# MainInterface.net
KiCad netlist of a schematic drawn in Altium Designer
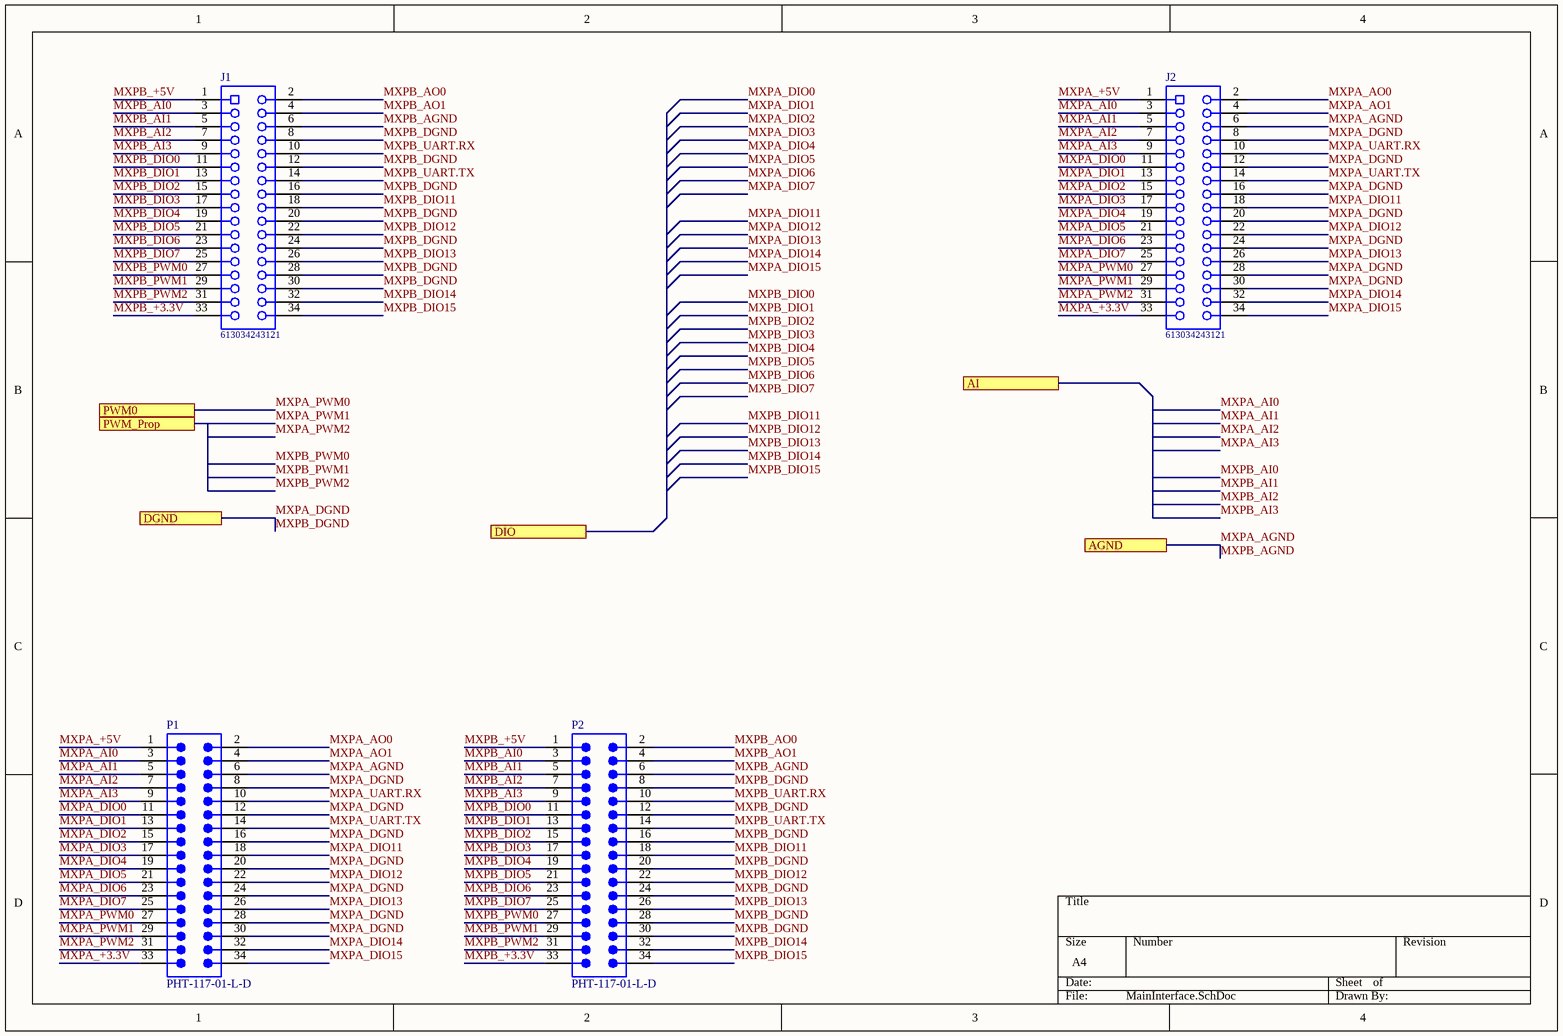
[diagram p0: MainInterface.SchDoc]

(export (version "E")
  (design (tool "Eeschema 10.0.6"))
  (components
    (comp (ref "J1")
      (value "613034243121")
      (footprint "613034243121")
      (description "THT Angled Socket Header WR-PHD, Pitch 2.54 mm, Dual Row, 34 pins")
      (fields (field (name "MANUFACTURER") "Wurth Elektronik") (field (name "PUBLISHER") "WurthElektronik"))
      (libsource (lib "Altium Content Vault") (part "WE-CN-2P-F-R34"))
    )
    (comp (ref "J2")
      (value "613034243121")
      (footprint "613034243121")
      (description "THT Angled Socket Header WR-PHD, Pitch 2.54 mm, Dual Row, 34 pins")
      (fields (field (name "MANUFACTURER") "Wurth Elektronik") (field (name "PUBLISHER") "WurthElektronik"))
      (libsource (lib "Altium Content Vault") (part "WE-CN-2P-F-R34"))
    )
    (comp (ref "P1")
      (value "PHT-117-01-L-D")
      (footprint "SMTC-PHT-117-01-X-D")
      (description "Press Fit Header, Through-hole, Vertical, -55 to 125 degC, 2.54 mm Pitch, 34-Pin, Male, RoHS")
      (fields (field (name "MANUFACTURER") "Samtec"))
      (libsource (lib "Altium Content Vault") (part "SMTC-PHT-117-01-X-D"))
    )
    (comp (ref "P2")
      (value "PHT-117-01-L-D")
      (footprint "SMTC-PHT-117-01-X-D")
      (description "Press Fit Header, Through-hole, Vertical, -55 to 125 degC, 2.54 mm Pitch, 34-Pin, Male, RoHS")
      (fields (field (name "MANUFACTURER") "Samtec"))
      (libsource (lib "Altium Content Vault") (part "SMTC-PHT-117-01-X-D"))
    )
  )
  (nets
    (net (code "3") (name "/MXPA_+3.3V") (class "Default")
      (node (ref "J2") (pin "33") (pinfunction "33_33") (pintype "passive"))
      (node (ref "P1") (pin "33") (pinfunction "33_33") (pintype "passive"))
    )
    (net (code "4") (name "/MXPA_+5V") (class "Default")
      (node (ref "J2") (pin "1") (pinfunction "1_1") (pintype "passive"))
      (node (ref "P1") (pin "1") (pinfunction "1_1") (pintype "passive"))
    )
    (net (code "5") (name "/MXPA_AGND") (class "Default")
      (node (ref "J1") (pin "6") (pinfunction "6_6") (pintype "passive"))
      (node (ref "J2") (pin "6") (pinfunction "6_6") (pintype "passive"))
      (node (ref "P1") (pin "6") (pinfunction "6_6") (pintype "passive"))
      (node (ref "P2") (pin "6") (pinfunction "6_6") (pintype "passive"))
    )
    (net (code "6") (name "/MXPA_AI0") (class "Default")
      (node (ref "J2") (pin "3") (pinfunction "3_3") (pintype "passive"))
      (node (ref "P1") (pin "3") (pinfunction "3_3") (pintype "passive"))
    )
    (net (code "7") (name "/MXPA_AI1") (class "Default")
      (node (ref "J2") (pin "5") (pinfunction "5_5") (pintype "passive"))
      (node (ref "P1") (pin "5") (pinfunction "5_5") (pintype "passive"))
    )
    (net (code "8") (name "/MXPA_AI2") (class "Default")
      (node (ref "J2") (pin "7") (pinfunction "7_7") (pintype "passive"))
      (node (ref "P1") (pin "7") (pinfunction "7_7") (pintype "passive"))
    )
    (net (code "9") (name "/MXPA_AI3") (class "Default")
      (node (ref "J2") (pin "9") (pinfunction "9_9") (pintype "passive"))
      (node (ref "P1") (pin "9") (pinfunction "9_9") (pintype "passive"))
    )
    (net (code "10") (name "/MXPA_AO0") (class "Default")
      (node (ref "J2") (pin "2") (pinfunction "2_2") (pintype "passive"))
      (node (ref "P1") (pin "2") (pinfunction "2_2") (pintype "passive"))
    )
    (net (code "11") (name "/MXPA_AO1") (class "Default")
      (node (ref "J2") (pin "4") (pinfunction "4_4") (pintype "passive"))
      (node (ref "P1") (pin "4") (pinfunction "4_4") (pintype "passive"))
    )
    (net (code "12") (name "/MXPA_DGND") (class "Default")
      (node (ref "J1") (pin "12") (pinfunction "12_12") (pintype "passive"))
      (node (ref "J1") (pin "16") (pinfunction "16_16") (pintype "passive"))
      (node (ref "J1") (pin "20") (pinfunction "20_20") (pintype "passive"))
      (node (ref "J1") (pin "24") (pinfunction "24_24") (pintype "passive"))
      (node (ref "J1") (pin "28") (pinfunction "28_28") (pintype "passive"))
      (node (ref "J1") (pin "30") (pinfunction "30_30") (pintype "passive"))
      (node (ref "J1") (pin "8") (pinfunction "8_8") (pintype "passive"))
      (node (ref "J2") (pin "12") (pinfunction "12_12") (pintype "passive"))
      (node (ref "J2") (pin "16") (pinfunction "16_16") (pintype "passive"))
      (node (ref "J2") (pin "20") (pinfunction "20_20") (pintype "passive"))
      (node (ref "J2") (pin "24") (pinfunction "24_24") (pintype "passive"))
      (node (ref "J2") (pin "28") (pinfunction "28_28") (pintype "passive"))
      (node (ref "J2") (pin "30") (pinfunction "30_30") (pintype "passive"))
      (node (ref "J2") (pin "8") (pinfunction "8_8") (pintype "passive"))
      (node (ref "P1") (pin "12") (pinfunction "12_12") (pintype "passive"))
      (node (ref "P1") (pin "16") (pinfunction "16_16") (pintype "passive"))
      (node (ref "P1") (pin "20") (pinfunction "20_20") (pintype "passive"))
      (node (ref "P1") (pin "24") (pinfunction "24_24") (pintype "passive"))
      (node (ref "P1") (pin "28") (pinfunction "28_28") (pintype "passive"))
      (node (ref "P1") (pin "30") (pinfunction "30_30") (pintype "passive"))
      (node (ref "P1") (pin "8") (pinfunction "8_8") (pintype "passive"))
      (node (ref "P2") (pin "12") (pinfunction "12_12") (pintype "passive"))
      (node (ref "P2") (pin "16") (pinfunction "16_16") (pintype "passive"))
      (node (ref "P2") (pin "20") (pinfunction "20_20") (pintype "passive"))
      (node (ref "P2") (pin "24") (pinfunction "24_24") (pintype "passive"))
      (node (ref "P2") (pin "28") (pinfunction "28_28") (pintype "passive"))
      (node (ref "P2") (pin "30") (pinfunction "30_30") (pintype "passive"))
      (node (ref "P2") (pin "8") (pinfunction "8_8") (pintype "passive"))
    )
    (net (code "13") (name "/MXPA_DIO0") (class "Default")
      (node (ref "J2") (pin "11") (pinfunction "11_11") (pintype "passive"))
      (node (ref "P1") (pin "11") (pinfunction "11_11") (pintype "passive"))
    )
    (net (code "14") (name "/MXPA_DIO1") (class "Default")
      (node (ref "J2") (pin "13") (pinfunction "13_13") (pintype "passive"))
      (node (ref "P1") (pin "13") (pinfunction "13_13") (pintype "passive"))
    )
    (net (code "15") (name "/MXPA_DIO2") (class "Default")
      (node (ref "J2") (pin "15") (pinfunction "15_15") (pintype "passive"))
      (node (ref "P1") (pin "15") (pinfunction "15_15") (pintype "passive"))
    )
    (net (code "16") (name "/MXPA_DIO3") (class "Default")
      (node (ref "J2") (pin "17") (pinfunction "17_17") (pintype "passive"))
      (node (ref "P1") (pin "17") (pinfunction "17_17") (pintype "passive"))
    )
    (net (code "17") (name "/MXPA_DIO4") (class "Default")
      (node (ref "J2") (pin "19") (pinfunction "19_19") (pintype "passive"))
      (node (ref "P1") (pin "19") (pinfunction "19_19") (pintype "passive"))
    )
    (net (code "18") (name "/MXPA_DIO5") (class "Default")
      (node (ref "J2") (pin "21") (pinfunction "21_21") (pintype "passive"))
      (node (ref "P1") (pin "21") (pinfunction "21_21") (pintype "passive"))
    )
    (net (code "19") (name "/MXPA_DIO6") (class "Default")
      (node (ref "J2") (pin "23") (pinfunction "23_23") (pintype "passive"))
      (node (ref "P1") (pin "23") (pinfunction "23_23") (pintype "passive"))
    )
    (net (code "20") (name "/MXPA_DIO7") (class "Default")
      (node (ref "J2") (pin "25") (pinfunction "25_25") (pintype "passive"))
      (node (ref "P1") (pin "25") (pinfunction "25_25") (pintype "passive"))
    )
    (net (code "21") (name "/MXPA_DIO11") (class "Default")
      (node (ref "J2") (pin "18") (pinfunction "18_18") (pintype "passive"))
      (node (ref "P1") (pin "18") (pinfunction "18_18") (pintype "passive"))
    )
    (net (code "22") (name "/MXPA_DIO12") (class "Default")
      (node (ref "J2") (pin "22") (pinfunction "22_22") (pintype "passive"))
      (node (ref "P1") (pin "22") (pinfunction "22_22") (pintype "passive"))
    )
    (net (code "23") (name "/MXPA_DIO13") (class "Default")
      (node (ref "J2") (pin "26") (pinfunction "26_26") (pintype "passive"))
      (node (ref "P1") (pin "26") (pinfunction "26_26") (pintype "passive"))
    )
    (net (code "24") (name "/MXPA_DIO14") (class "Default")
      (node (ref "J2") (pin "32") (pinfunction "32_32") (pintype "passive"))
      (node (ref "P1") (pin "32") (pinfunction "32_32") (pintype "passive"))
    )
    (net (code "25") (name "/MXPA_DIO15") (class "Default")
      (node (ref "J2") (pin "34") (pinfunction "34_34") (pintype "passive"))
      (node (ref "P1") (pin "34") (pinfunction "34_34") (pintype "passive"))
    )
    (net (code "26") (name "/MXPA_PWM0") (class "Default")
      (node (ref "J2") (pin "27") (pinfunction "27_27") (pintype "passive"))
      (node (ref "P1") (pin "27") (pinfunction "27_27") (pintype "passive"))
    )
    (net (code "27") (name "/MXPA_PWM1") (class "Default")
      (node (ref "J2") (pin "29") (pinfunction "29_29") (pintype "passive"))
      (node (ref "P1") (pin "29") (pinfunction "29_29") (pintype "passive"))
    )
    (net (code "28") (name "/MXPA_PWM2") (class "Default")
      (node (ref "J2") (pin "31") (pinfunction "31_31") (pintype "passive"))
      (node (ref "P1") (pin "31") (pinfunction "31_31") (pintype "passive"))
    )
    (net (code "29") (name "/MXPA_UART.RX") (class "Default")
      (node (ref "J2") (pin "10") (pinfunction "10_10") (pintype "passive"))
      (node (ref "P1") (pin "10") (pinfunction "10_10") (pintype "passive"))
    )
    (net (code "30") (name "/MXPA_UART.TX") (class "Default")
      (node (ref "J2") (pin "14") (pinfunction "14_14") (pintype "passive"))
      (node (ref "P1") (pin "14") (pinfunction "14_14") (pintype "passive"))
    )
    (net (code "31") (name "/MXPB_+3.3V") (class "Default")
      (node (ref "J1") (pin "33") (pinfunction "33_33") (pintype "passive"))
      (node (ref "P2") (pin "33") (pinfunction "33_33") (pintype "passive"))
    )
    (net (code "32") (name "/MXPB_+5V") (class "Default")
      (node (ref "J1") (pin "1") (pinfunction "1_1") (pintype "passive"))
      (node (ref "P2") (pin "1") (pinfunction "1_1") (pintype "passive"))
    )
    (net (code "33") (name "/MXPB_AI0") (class "Default")
      (node (ref "J1") (pin "3") (pinfunction "3_3") (pintype "passive"))
      (node (ref "P2") (pin "3") (pinfunction "3_3") (pintype "passive"))
    )
    (net (code "34") (name "/MXPB_AI1") (class "Default")
      (node (ref "J1") (pin "5") (pinfunction "5_5") (pintype "passive"))
      (node (ref "P2") (pin "5") (pinfunction "5_5") (pintype "passive"))
    )
    (net (code "35") (name "/MXPB_AI2") (class "Default")
      (node (ref "J1") (pin "7") (pinfunction "7_7") (pintype "passive"))
      (node (ref "P2") (pin "7") (pinfunction "7_7") (pintype "passive"))
    )
    (net (code "36") (name "/MXPB_AI3") (class "Default")
      (node (ref "J1") (pin "9") (pinfunction "9_9") (pintype "passive"))
      (node (ref "P2") (pin "9") (pinfunction "9_9") (pintype "passive"))
    )
    (net (code "37") (name "/MXPB_AO0") (class "Default")
      (node (ref "J1") (pin "2") (pinfunction "2_2") (pintype "passive"))
      (node (ref "P2") (pin "2") (pinfunction "2_2") (pintype "passive"))
    )
    (net (code "38") (name "/MXPB_AO1") (class "Default")
      (node (ref "J1") (pin "4") (pinfunction "4_4") (pintype "passive"))
      (node (ref "P2") (pin "4") (pinfunction "4_4") (pintype "passive"))
    )
    (net (code "39") (name "/MXPB_DIO0") (class "Default")
      (node (ref "J1") (pin "11") (pinfunction "11_11") (pintype "passive"))
      (node (ref "P2") (pin "11") (pinfunction "11_11") (pintype "passive"))
    )
    (net (code "40") (name "/MXPB_DIO1") (class "Default")
      (node (ref "J1") (pin "13") (pinfunction "13_13") (pintype "passive"))
      (node (ref "P2") (pin "13") (pinfunction "13_13") (pintype "passive"))
    )
    (net (code "41") (name "/MXPB_DIO2") (class "Default")
      (node (ref "J1") (pin "15") (pinfunction "15_15") (pintype "passive"))
      (node (ref "P2") (pin "15") (pinfunction "15_15") (pintype "passive"))
    )
    (net (code "42") (name "/MXPB_DIO3") (class "Default")
      (node (ref "J1") (pin "17") (pinfunction "17_17") (pintype "passive"))
      (node (ref "P2") (pin "17") (pinfunction "17_17") (pintype "passive"))
    )
    (net (code "43") (name "/MXPB_DIO4") (class "Default")
      (node (ref "J1") (pin "19") (pinfunction "19_19") (pintype "passive"))
      (node (ref "P2") (pin "19") (pinfunction "19_19") (pintype "passive"))
    )
    (net (code "44") (name "/MXPB_DIO5") (class "Default")
      (node (ref "J1") (pin "21") (pinfunction "21_21") (pintype "passive"))
      (node (ref "P2") (pin "21") (pinfunction "21_21") (pintype "passive"))
    )
    (net (code "45") (name "/MXPB_DIO6") (class "Default")
      (node (ref "J1") (pin "23") (pinfunction "23_23") (pintype "passive"))
      (node (ref "P2") (pin "23") (pinfunction "23_23") (pintype "passive"))
    )
    (net (code "46") (name "/MXPB_DIO7") (class "Default")
      (node (ref "J1") (pin "25") (pinfunction "25_25") (pintype "passive"))
      (node (ref "P2") (pin "25") (pinfunction "25_25") (pintype "passive"))
    )
    (net (code "47") (name "/MXPB_DIO11") (class "Default")
      (node (ref "J1") (pin "18") (pinfunction "18_18") (pintype "passive"))
      (node (ref "P2") (pin "18") (pinfunction "18_18") (pintype "passive"))
    )
    (net (code "48") (name "/MXPB_DIO12") (class "Default")
      (node (ref "J1") (pin "22") (pinfunction "22_22") (pintype "passive"))
      (node (ref "P2") (pin "22") (pinfunction "22_22") (pintype "passive"))
    )
    (net (code "49") (name "/MXPB_DIO13") (class "Default")
      (node (ref "J1") (pin "26") (pinfunction "26_26") (pintype "passive"))
      (node (ref "P2") (pin "26") (pinfunction "26_26") (pintype "passive"))
    )
    (net (code "50") (name "/MXPB_DIO14") (class "Default")
      (node (ref "J1") (pin "32") (pinfunction "32_32") (pintype "passive"))
      (node (ref "P2") (pin "32") (pinfunction "32_32") (pintype "passive"))
    )
    (net (code "51") (name "/MXPB_DIO15") (class "Default")
      (node (ref "J1") (pin "34") (pinfunction "34_34") (pintype "passive"))
      (node (ref "P2") (pin "34") (pinfunction "34_34") (pintype "passive"))
    )
    (net (code "52") (name "/MXPB_PWM0") (class "Default")
      (node (ref "J1") (pin "27") (pinfunction "27_27") (pintype "passive"))
      (node (ref "P2") (pin "27") (pinfunction "27_27") (pintype "passive"))
    )
    (net (code "53") (name "/MXPB_PWM1") (class "Default")
      (node (ref "J1") (pin "29") (pinfunction "29_29") (pintype "passive"))
      (node (ref "P2") (pin "29") (pinfunction "29_29") (pintype "passive"))
    )
    (net (code "54") (name "/MXPB_PWM2") (class "Default")
      (node (ref "J1") (pin "31") (pinfunction "31_31") (pintype "passive"))
      (node (ref "P2") (pin "31") (pinfunction "31_31") (pintype "passive"))
    )
    (net (code "55") (name "/MXPB_UART.RX") (class "Default")
      (node (ref "J1") (pin "10") (pinfunction "10_10") (pintype "passive"))
      (node (ref "P2") (pin "10") (pinfunction "10_10") (pintype "passive"))
    )
    (net (code "56") (name "/MXPB_UART.TX") (class "Default")
      (node (ref "J1") (pin "14") (pinfunction "14_14") (pintype "passive"))
      (node (ref "P2") (pin "14") (pinfunction "14_14") (pintype "passive"))
    )
  )
)
